# Microcontroller.net
KiCad netlist of a schematic drawn in Altium Designer
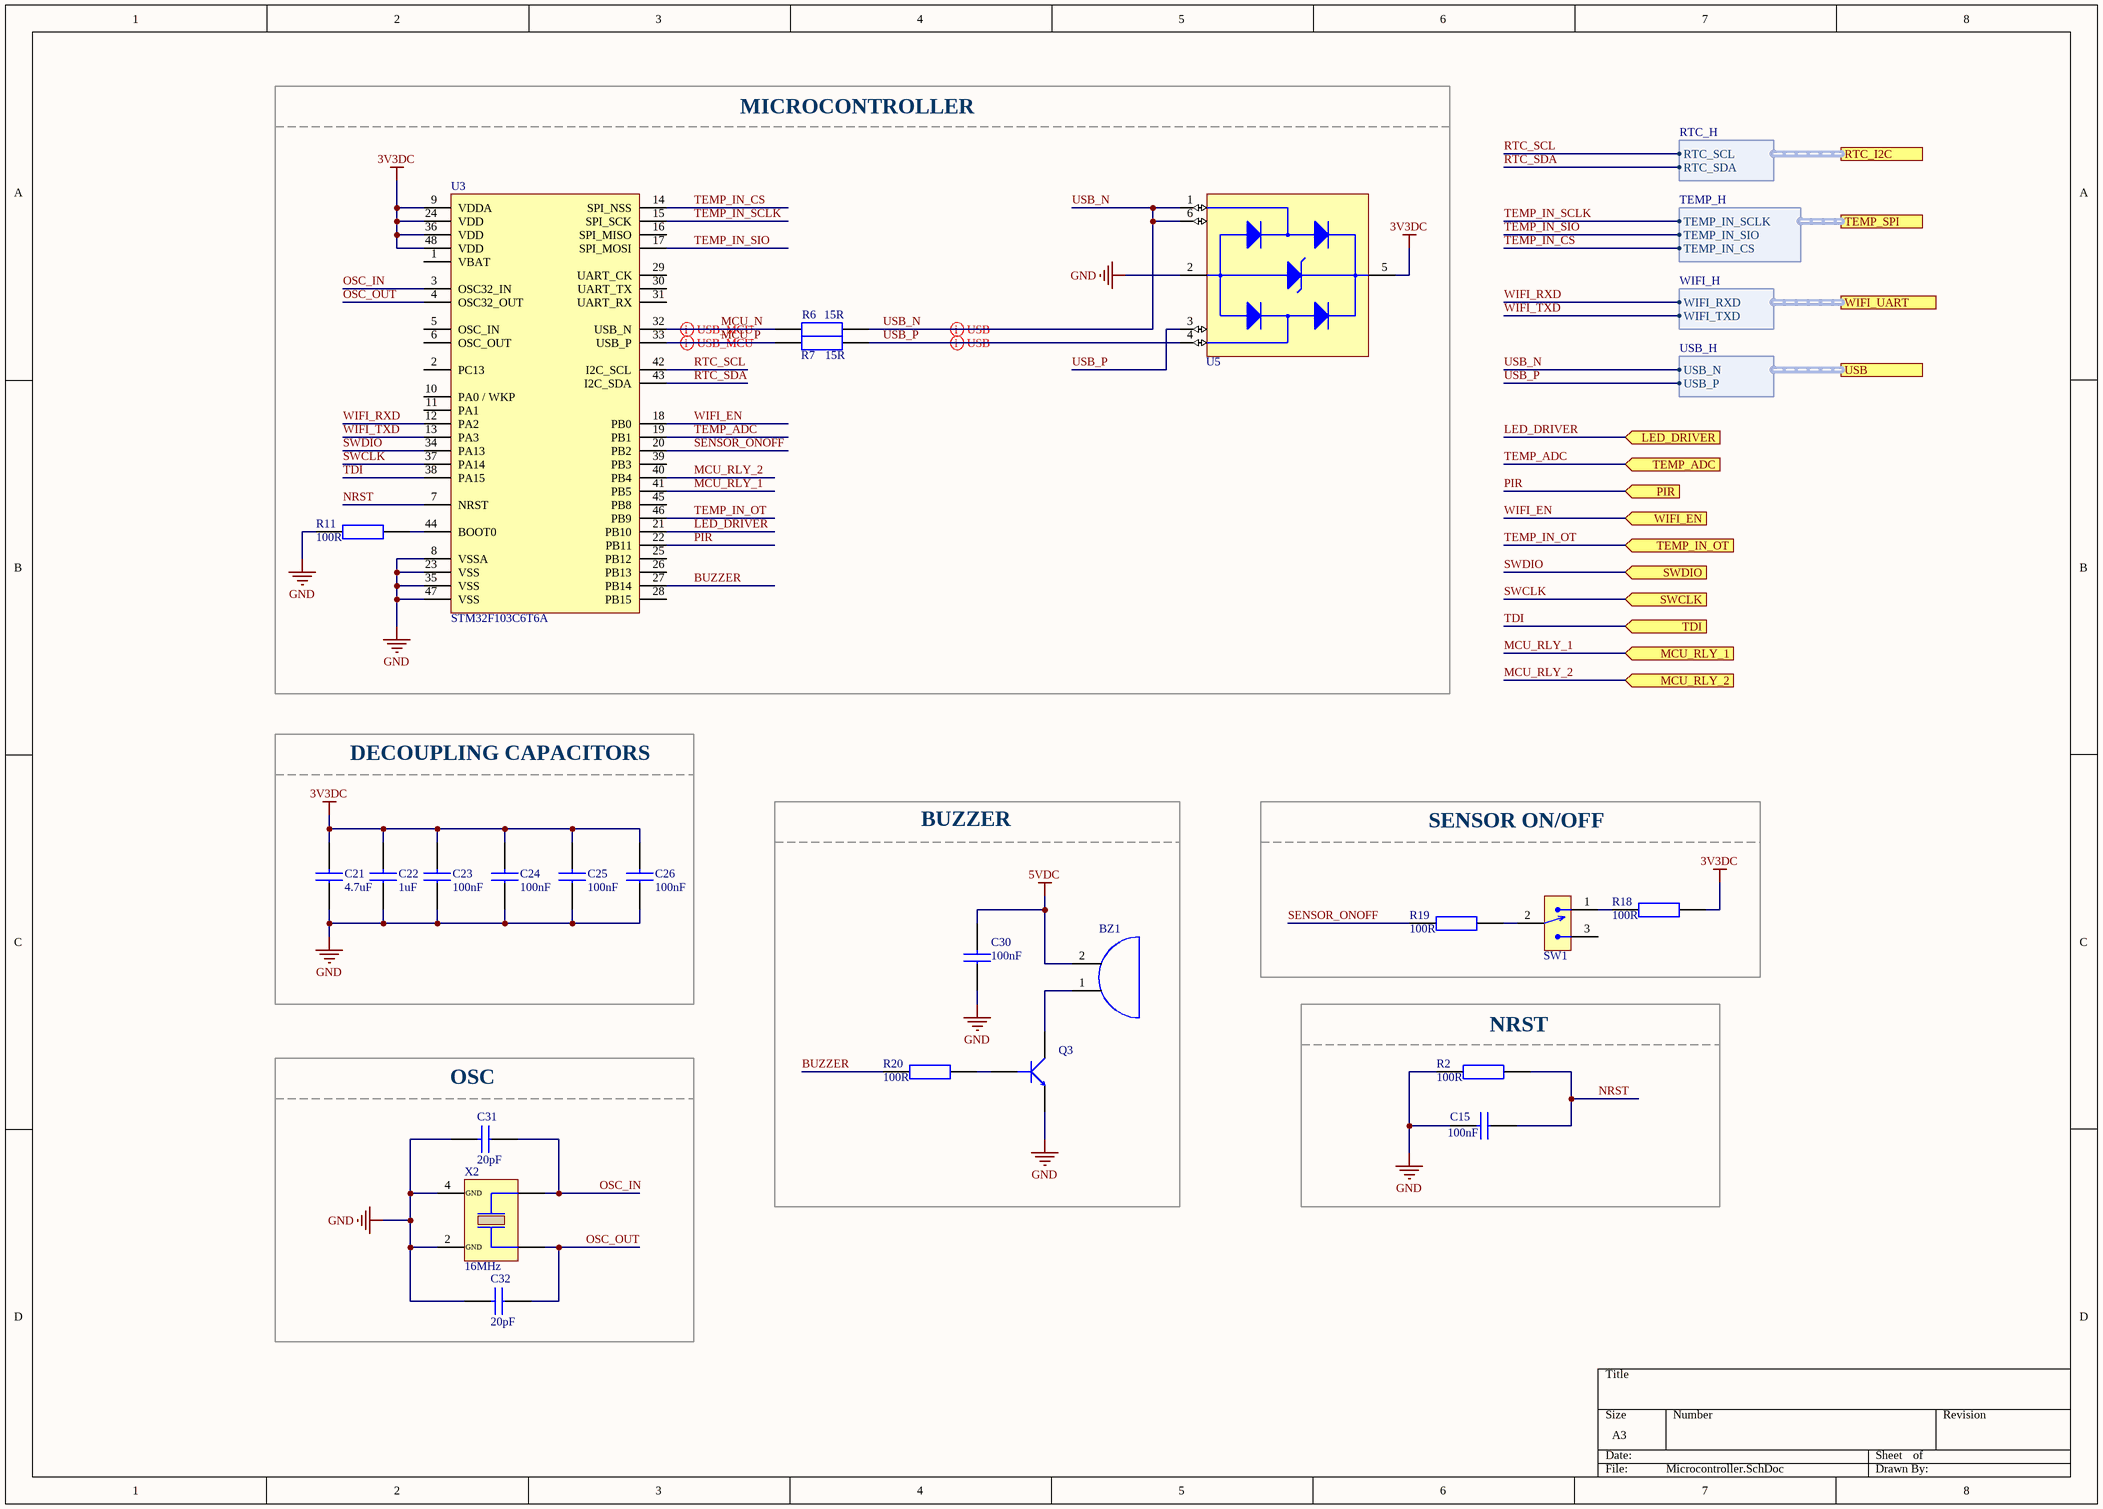
[diagram p0: Microcontroller.SchDoc]

(export (version "E")
  (design (tool "Eeschema 10.0.6"))
  (components
    (comp (ref "BZ1")
      (value "CMI-9605IC-0580T")
      (footprint "CMI-9605IC")
      (description "Buzzers Indicator, Internally Driven Magnetic 5V 30mA 2.7kHz 80dB @ 5V, 10cm Through Hole PC Pins")
      (fields (field (name "MANUFACTURER") "CUI Devices") (field (name "DESIGNED BY") "BERK"))
      (libsource (lib "GuvenlikSistemi_Library") (part "CMI-9605IC-0580T"))
    )
    (comp (ref "C15")
      (value "C0603C104K5RACTU")
      (footprint "CAP_0603")
      (description "CAP CER 100nF %10 0603 SMD")
      (fields
        (field (name "MANUFACTURER") "KEMET")
        (field (name "TOLERANCE") "10%")
        (field (name "CAPACITANCE") "100nF")
        (field (name "DESIGNED BY") "BERK")
      )
      (libsource (lib "GuvenlikSistemi_Library") (part "CAP CER 100nF 0603"))
    )
    (comp (ref "C21")
      (value "CL21A475KAQNNNE")
      (footprint "CAP_0805")
      (description "CAP CER 4.7uF %10 0805")
      (fields
        (field (name "MANUFACTURER") "Samsung")
        (field (name "TOLERANCE") "10%")
        (field (name "CAPACITANCE") "4.7uF")
        (field (name "DESIGNED BY") "BERK")
      )
      (libsource (lib "GuvenlikSistemi_Library") (part "CAP CER 4.7uF 0805"))
    )
    (comp (ref "C22")
      (value "CL21B105KBFNNNE")
      (footprint "CAP_0805")
      (description "CAP CER 1uF %10 0805")
      (fields
        (field (name "MANUFACTURER") "Samsung")
        (field (name "TOLERANCE") "10%")
        (field (name "CAPACITANCE") "1uF")
        (field (name "DESIGNED BY") "BERK")
      )
      (libsource (lib "GuvenlikSistemi_Library") (part "CAP CER 1uF 0805"))
    )
    (comp (ref "C23")
      (value "C0603C104K5RACTU")
      (footprint "CAP_0603")
      (description "CAP CER 100nF %10 0603 SMD")
      (fields
        (field (name "MANUFACTURER") "KEMET")
        (field (name "TOLERANCE") "10%")
        (field (name "CAPACITANCE") "100nF")
        (field (name "DESIGNED BY") "BERK")
      )
      (libsource (lib "GuvenlikSistemi_Library") (part "CAP CER 100nF 0603"))
    )
    (comp (ref "C24")
      (value "C0603C104K5RACTU")
      (footprint "CAP_0603")
      (description "CAP CER 100nF %10 0603 SMD")
      (fields
        (field (name "MANUFACTURER") "KEMET")
        (field (name "TOLERANCE") "10%")
        (field (name "CAPACITANCE") "100nF")
        (field (name "DESIGNED BY") "BERK")
      )
      (libsource (lib "GuvenlikSistemi_Library") (part "CAP CER 100nF 0603"))
    )
    (comp (ref "C25")
      (value "C0603C104K5RACTU")
      (footprint "CAP_0603")
      (description "CAP CER 100nF %10 0603 SMD")
      (fields
        (field (name "MANUFACTURER") "KEMET")
        (field (name "TOLERANCE") "10%")
        (field (name "CAPACITANCE") "100nF")
        (field (name "DESIGNED BY") "BERK")
      )
      (libsource (lib "GuvenlikSistemi_Library") (part "CAP CER 100nF 0603"))
    )
    (comp (ref "C26")
      (value "C0603C104K5RACTU")
      (footprint "CAP_0603")
      (description "CAP CER 100nF %10 0603 SMD")
      (fields
        (field (name "MANUFACTURER") "KEMET")
        (field (name "TOLERANCE") "10%")
        (field (name "CAPACITANCE") "100nF")
        (field (name "DESIGNED BY") "BERK")
      )
      (libsource (lib "GuvenlikSistemi_Library") (part "CAP CER 100nF 0603"))
    )
    (comp (ref "C30")
      (value "CL21B104KBCNNNC")
      (footprint "CAP_0805")
      (description "CAP CER 100nF %10 0805")
      (fields
        (field (name "MANUFACTURER") "Samsung")
        (field (name "TOLERANCE") "10%")
        (field (name "CAPACITANCE") "100nF")
        (field (name "DESIGNED BY") "BERK")
      )
      (libsource (lib "GuvenlikSistemi_Library") (part "CAP CER 100nF 0805"))
    )
    (comp (ref "C31")
      (value "CL10C200JB8NNNC")
      (footprint "CAP_0603")
      (description "CAP CER 20pF %5 0603 SMD")
      (fields
        (field (name "MANUFACTURER") "Samsung")
        (field (name "TOLERANCE") "5%")
        (field (name "CAPACITANCE") "20pF")
        (field (name "DESIGNED BY") "BERK")
      )
      (libsource (lib "GuvenlikSistemi_Library") (part "CAP CER 20pF 0603"))
    )
    (comp (ref "C32")
      (value "CL10C200JB8NNNC")
      (footprint "CAP_0603")
      (description "CAP CER 20pF %5 0603 SMD")
      (fields
        (field (name "MANUFACTURER") "Samsung")
        (field (name "TOLERANCE") "5%")
        (field (name "CAPACITANCE") "20pF")
        (field (name "DESIGNED BY") "BERK")
      )
      (libsource (lib "GuvenlikSistemi_Library") (part "CAP CER 20pF 0603"))
    )
    (comp (ref "Q3")
      (value "MMBT3904-7-F")
      (footprint "SOT-23F")
      (description "Transistor General Purpose BJT NPN 40 Volt 0.2A Automotive 3-Pin SOT-23")
      (fields (field (name "MANUFACTURER") "Diodes Zetex") (field (name "DESIGNED BY") "BERK"))
      (libsource (lib "GuvenlikSistemi_Library") (part "MMBT3904-7-F"))
    )
    (comp (ref "R2")
      (value "RC0603JR-07100RL")
      (footprint "RES_0603")
      (description "RES 100 %5 OHM 0603 SMD")
      (fields
        (field (name "MANUFACTURER") "Yageo")
        (field (name "TOLERANCE") "5%")
        (field (name "RESISTANCE") "100R")
        (field (name "DESIGNED BY") "BERK")
      )
      (libsource (lib "GuvenlikSistemi_Library") (part "RES 100 OHM 0603"))
    )
    (comp (ref "R6")
      (value "RC0603JR-0715RL")
      (footprint "RES_0603")
      (description "RES 15 %5 OHM 0603 SMD")
      (fields
        (field (name "MANUFACTURER") "Yageo")
        (field (name "TOLERANCE") "5%")
        (field (name "RESISTANCE") "15R")
        (field (name "DESIGNED BY") "BERK")
      )
      (libsource (lib "GuvenlikSistemi_Library") (part "RES 15 OHM 0603"))
    )
    (comp (ref "R7")
      (value "RC0603JR-0715RL")
      (footprint "RES_0603")
      (description "RES 15 %5 OHM 0603 SMD")
      (fields
        (field (name "MANUFACTURER") "Yageo")
        (field (name "TOLERANCE") "5%")
        (field (name "RESISTANCE") "15R")
        (field (name "DESIGNED BY") "BERK")
      )
      (libsource (lib "GuvenlikSistemi_Library") (part "RES 15 OHM 0603"))
    )
    (comp (ref "R11")
      (value "RC0603JR-07100RL")
      (footprint "RES_0603")
      (description "RES 100 %5 OHM 0603 SMD")
      (fields
        (field (name "MANUFACTURER") "Yageo")
        (field (name "TOLERANCE") "5%")
        (field (name "RESISTANCE") "100R")
        (field (name "DESIGNED BY") "BERK")
      )
      (libsource (lib "GuvenlikSistemi_Library") (part "RES 100 OHM 0603"))
    )
    (comp (ref "R18")
      (value "RC0603JR-07100RL")
      (footprint "RES_0603")
      (description "RES 100 %5 OHM 0603 SMD")
      (fields
        (field (name "MANUFACTURER") "Yageo")
        (field (name "TOLERANCE") "5%")
        (field (name "RESISTANCE") "100R")
        (field (name "DESIGNED BY") "BERK")
      )
      (libsource (lib "GuvenlikSistemi_Library") (part "RES 100 OHM 0603"))
    )
    (comp (ref "R19")
      (value "RC0603JR-07100RL")
      (footprint "RES_0603")
      (description "RES 100 %5 OHM 0603 SMD")
      (fields
        (field (name "MANUFACTURER") "Yageo")
        (field (name "TOLERANCE") "5%")
        (field (name "RESISTANCE") "100R")
        (field (name "DESIGNED BY") "BERK")
      )
      (libsource (lib "") (part "RES 100 OHM 0603_1"))
    )
    (comp (ref "R20")
      (value "RC0603JR-07100RL")
      (footprint "RES_0603")
      (description "RES 100 %5 OHM 0603 SMD")
      (fields
        (field (name "MANUFACTURER") "Yageo")
        (field (name "TOLERANCE") "5%")
        (field (name "RESISTANCE") "100R")
        (field (name "DESIGNED BY") "BERK")
      )
      (libsource (lib "GuvenlikSistemi_Library") (part "RES 100 OHM 0603"))
    )
    (comp (ref "SW1")
      (value "EG1215AA")
      (footprint "EG1215AA")
      (description "Slide Switch, SPDT, 0.025A, 24V, SMD")
      (fields
        (field (name "MANUFACTURER") "E-Switch")
        (field (name "TOLERANCE") "4.95%")
        (field (name "DESIGNED BY") "BERK")
      )
      (libsource (lib "GuvenlikSistemi_Library") (part "EG1215AA"))
    )
    (comp (ref "U3")
      (value "STM32F103C6T6A")
      (footprint "LQFP-48")
      (description "MCU 32-bit STM32F ARM Cortex M3 RISC 32KB Flash 2.5V/3.3V 48-Pin LQFP Tray")
      (fields (field (name "MANUFACTURER") "STMicroelectronics") (field (name "DESIGNED BY") "BERK"))
      (libsource (lib "GuvenlikSistemi_Library") (part "STM32F103C6T6A"))
    )
    (comp (ref "U5")
      (value "USBLC6-2SC6")
      (footprint "SOT23-6L")
      (description "TVS DIODE 5.25V 17V SOT23-6")
      (fields (field (name "MANUFACTURER") "STMicroelectronics") (field (name "DESIGNED BY") "BERK"))
      (libsource (lib "GuvenlikSistemi_Library") (part "USB PROTECTION"))
    )
    (comp (ref "X2")
      (value "ECS-160-20-30B-TR")
      (footprint "ECS")
      (description "CRYSTAL 16.0000MHZ 20PF SMD")
      (fields
        (field (name "MANUFACTURER") "ECS International")
        (field (name "TOLERANCE") "50ppm")
        (field (name "FREQUENCY") "16MHz")
        (field (name "DESIGNED BY") "BERK")
      )
      (libsource (lib "GuvenlikSistemi_Library") (part "CRYSTAL 16MHz"))
    )
  )
  (nets
    (net (code "5") (name "/BUZZER") (class "Default")
      (node (ref "R20") (pin "1") (pinfunction "1_1") (pintype "passive"))
      (node (ref "U3") (pin "27") (pinfunction "PB14_27") (pintype "passive"))
    )
    (net (code "6") (name "/LED_DRIVER") (class "Default")
      (node (ref "U3") (pin "21") (pinfunction "PB10_21") (pintype "passive"))
    )
    (net (code "7") (name "/MCU_N") (class "Default")
      (node (ref "R6") (pin "1") (pinfunction "1_1") (pintype "passive"))
      (node (ref "U3") (pin "32") (pinfunction "USB_N_32") (pintype "passive"))
    )
    (net (code "8") (name "/MCU_P") (class "Default")
      (node (ref "R7") (pin "1") (pinfunction "1_1") (pintype "passive"))
      (node (ref "U3") (pin "33") (pinfunction "USB_P_33") (pintype "passive"))
    )
    (net (code "9") (name "/MCU_RLY_1") (class "Default")
      (node (ref "U3") (pin "41") (pinfunction "PB5_41") (pintype "passive"))
    )
    (net (code "10") (name "/MCU_RLY_2") (class "Default")
      (node (ref "U3") (pin "40") (pinfunction "PB4_40") (pintype "passive"))
    )
    (net (code "11") (name "/NRST") (class "Default")
      (node (ref "C15") (pin "1") (pinfunction "1_1") (pintype "passive"))
      (node (ref "R2") (pin "2") (pinfunction "2_2") (pintype "passive"))
      (node (ref "U3") (pin "7") (pinfunction "NRST_7") (pintype "passive"))
    )
    (net (code "12") (name "/OSC_IN") (class "Default")
      (node (ref "C31") (pin "1") (pinfunction "1_1") (pintype "passive"))
      (node (ref "U3") (pin "3") (pinfunction "OSC32_IN_3") (pintype "passive"))
      (node (ref "X2") (pin "3") (pinfunction "3_3") (pintype "passive"))
    )
    (net (code "13") (name "/OSC_OUT") (class "Default")
      (node (ref "C32") (pin "1") (pinfunction "1_1") (pintype "passive"))
      (node (ref "U3") (pin "4") (pinfunction "OSC32_OUT_4") (pintype "passive"))
      (node (ref "X2") (pin "1") (pinfunction "1_1") (pintype "passive"))
    )
    (net (code "14") (name "/PIR") (class "Default")
      (node (ref "U3") (pin "22") (pinfunction "PB11_22") (pintype "passive"))
    )
    (net (code "15") (name "/RTC_SCL") (class "Default")
      (node (ref "U3") (pin "42") (pinfunction "I2C_SCL_42") (pintype "passive"))
    )
    (net (code "16") (name "/RTC_SDA") (class "Default")
      (node (ref "U3") (pin "43") (pinfunction "I2C_SDA_43") (pintype "passive"))
    )
    (net (code "17") (name "/SENSOR_ONOFF") (class "Default")
      (node (ref "R19") (pin "2") (pinfunction "2_2") (pintype "passive"))
      (node (ref "U3") (pin "20") (pinfunction "PB2_20") (pintype "passive"))
    )
    (net (code "18") (name "/SWCLK") (class "Default")
      (node (ref "U3") (pin "37") (pinfunction "PA14_37") (pintype "passive"))
    )
    (net (code "19") (name "/SWDIO") (class "Default")
      (node (ref "U3") (pin "34") (pinfunction "PA13_34") (pintype "passive"))
    )
    (net (code "20") (name "/TDI") (class "Default")
      (node (ref "U3") (pin "38") (pinfunction "PA15_38") (pintype "passive"))
    )
    (net (code "21") (name "/TEMP_ADC") (class "Default")
      (node (ref "U3") (pin "19") (pinfunction "PB1_19") (pintype "passive"))
    )
    (net (code "22") (name "/TEMP_IN_CS") (class "Default")
      (node (ref "U3") (pin "14") (pinfunction "SPI_NSS_14") (pintype "passive"))
    )
    (net (code "23") (name "/TEMP_IN_OT") (class "Default")
      (node (ref "U3") (pin "46") (pinfunction "PB9_46") (pintype "passive"))
    )
    (net (code "24") (name "/TEMP_IN_SCLK") (class "Default")
      (node (ref "U3") (pin "15") (pinfunction "SPI_SCK_15") (pintype "passive"))
    )
    (net (code "25") (name "/TEMP_IN_SIO") (class "Default")
      (node (ref "U3") (pin "17") (pinfunction "SPI_MOSI_17") (pintype "passive"))
    )
    (net (code "26") (name "/USB_N") (class "Default")
      (node (ref "R6") (pin "2") (pinfunction "2_2") (pintype "passive"))
      (node (ref "U5") (pin "1") (pinfunction "I/O1_1") (pintype "bidirectional"))
      (node (ref "U5") (pin "6") (pinfunction "I/O1_6") (pintype "bidirectional"))
    )
    (net (code "27") (name "/USB_P") (class "Default")
      (node (ref "R7") (pin "2") (pinfunction "2_2") (pintype "passive"))
      (node (ref "U5") (pin "3") (pinfunction "I/O2_3") (pintype "bidirectional"))
      (node (ref "U5") (pin "4") (pinfunction "I/O2_4") (pintype "bidirectional"))
    )
    (net (code "28") (name "/WIFI_EN") (class "Default")
      (node (ref "U3") (pin "18") (pinfunction "PB0_18") (pintype "passive"))
    )
    (net (code "29") (name "/WIFI_RXD") (class "Default")
      (node (ref "U3") (pin "12") (pinfunction "PA2_12") (pintype "passive"))
    )
    (net (code "30") (name "/WIFI_TXD") (class "Default")
      (node (ref "U3") (pin "13") (pinfunction "PA3_13") (pintype "passive"))
    )
    (net (code "35") (name "3V3DC") (class "Default")
      (node (ref "C21") (pin "2") (pinfunction "2_2") (pintype "passive"))
      (node (ref "C22") (pin "2") (pinfunction "2_2") (pintype "passive"))
      (node (ref "C23") (pin "2") (pinfunction "2_2") (pintype "passive"))
      (node (ref "C24") (pin "2") (pinfunction "2_2") (pintype "passive"))
      (node (ref "C25") (pin "2") (pinfunction "2_2") (pintype "passive"))
      (node (ref "C26") (pin "2") (pinfunction "2_2") (pintype "passive"))
      (node (ref "R18") (pin "2") (pinfunction "2_2") (pintype "passive"))
      (node (ref "U3") (pin "24") (pinfunction "VDD_24") (pintype "passive"))
      (node (ref "U3") (pin "36") (pinfunction "VDD_36") (pintype "passive"))
      (node (ref "U3") (pin "48") (pinfunction "VDD_48") (pintype "passive"))
      (node (ref "U3") (pin "9") (pinfunction "VDDA_9") (pintype "passive"))
      (node (ref "U5") (pin "5") (pinfunction "VBUS_5") (pintype "power_in"))
    )
    (net (code "36") (name "5VDC") (class "Default")
      (node (ref "BZ1") (pin "2") (pinfunction "2_2") (pintype "passive"))
      (node (ref "C30") (pin "2") (pinfunction "2_2") (pintype "passive"))
    )
    (net (code "37") (name "GND") (class "Default")
      (node (ref "C15") (pin "2") (pinfunction "2_2") (pintype "passive"))
      (node (ref "C21") (pin "1") (pinfunction "1_1") (pintype "passive"))
      (node (ref "C22") (pin "1") (pinfunction "1_1") (pintype "passive"))
      (node (ref "C23") (pin "1") (pinfunction "1_1") (pintype "passive"))
      (node (ref "C24") (pin "1") (pinfunction "1_1") (pintype "passive"))
      (node (ref "C25") (pin "1") (pinfunction "1_1") (pintype "passive"))
      (node (ref "C26") (pin "1") (pinfunction "1_1") (pintype "passive"))
      (node (ref "C30") (pin "1") (pinfunction "1_1") (pintype "passive"))
      (node (ref "C31") (pin "2") (pinfunction "2_2") (pintype "passive"))
      (node (ref "C32") (pin "2") (pinfunction "2_2") (pintype "passive"))
      (node (ref "Q3") (pin "2") (pinfunction "E_2") (pintype "power_in"))
      (node (ref "R11") (pin "1") (pinfunction "1_1") (pintype "passive"))
      (node (ref "R2") (pin "1") (pinfunction "1_1") (pintype "passive"))
      (node (ref "U3") (pin "23") (pinfunction "VSS_23") (pintype "passive"))
      (node (ref "U3") (pin "35") (pinfunction "VSS_35") (pintype "passive"))
      (node (ref "U3") (pin "47") (pinfunction "VSS_47") (pintype "passive"))
      (node (ref "U3") (pin "8") (pinfunction "VSSA_8") (pintype "passive"))
      (node (ref "U5") (pin "2") (pinfunction "GND_2") (pintype "power_in"))
      (node (ref "X2") (pin "2") (pinfunction "GND_2") (pintype "passive"))
      (node (ref "X2") (pin "4") (pinfunction "GND_4") (pintype "passive"))
    )
    (net (code "38") (name "Net-(Q3-B)") (class "Default")
      (node (ref "Q3") (pin "1") (pinfunction "B_1") (pintype "power_in"))
      (node (ref "R20") (pin "2") (pinfunction "2_2") (pintype "passive"))
    )
    (net (code "39") (name "Net-(Q3-C)") (class "Default")
      (node (ref "BZ1") (pin "1") (pinfunction "1_1") (pintype "passive"))
      (node (ref "Q3") (pin "3") (pinfunction "C_3") (pintype "power_in"))
    )
    (net (code "40") (name "Net-(R18-Pad1)") (class "Default")
      (node (ref "R18") (pin "1") (pinfunction "1_1") (pintype "passive"))
      (node (ref "SW1") (pin "1") (pinfunction "1_1") (pintype "passive"))
    )
    (net (code "41") (name "Net-(R19-Pad1)") (class "Default")
      (node (ref "R19") (pin "1") (pinfunction "1_1") (pintype "passive"))
      (node (ref "SW1") (pin "2") (pinfunction "2_2") (pintype "passive"))
    )
    (net (code "42") (name "Net-(U3-BOOT0)") (class "Default")
      (node (ref "R11") (pin "2") (pinfunction "2_2") (pintype "passive"))
      (node (ref "U3") (pin "44") (pinfunction "BOOT0_44") (pintype "passive"))
    )
    (net (code "43") (name "unconnected-(SW1-Pad3)") (class "Default")
      (node (ref "SW1") (pin "3") (pinfunction "3_3") (pintype "passive"))
    )
    (net (code "44") (name "unconnected-(U3-OSC_IN-Pad5)") (class "Default")
      (node (ref "U3") (pin "5") (pinfunction "OSC_IN_5") (pintype "passive"))
    )
    (net (code "45") (name "unconnected-(U3-OSC_OUT-Pad6)") (class "Default")
      (node (ref "U3") (pin "6") (pinfunction "OSC_OUT_6") (pintype "passive"))
    )
    (net (code "46") (name "unconnected-(U3-PA0_{slash}_WKP-Pad10)") (class "Default")
      (node (ref "U3") (pin "10") (pinfunction "PA0_/_WKP_10") (pintype "passive"))
    )
    (net (code "47") (name "unconnected-(U3-PA1-Pad11)") (class "Default")
      (node (ref "U3") (pin "11") (pinfunction "PA1_11") (pintype "passive"))
    )
    (net (code "48") (name "unconnected-(U3-PB3-Pad39)") (class "Default")
      (node (ref "U3") (pin "39") (pinfunction "PB3_39") (pintype "passive"))
    )
    (net (code "49") (name "unconnected-(U3-PB8-Pad45)") (class "Default")
      (node (ref "U3") (pin "45") (pinfunction "PB8_45") (pintype "passive"))
    )
    (net (code "50") (name "unconnected-(U3-PB12-Pad25)") (class "Default")
      (node (ref "U3") (pin "25") (pinfunction "PB12_25") (pintype "passive"))
    )
    (net (code "51") (name "unconnected-(U3-PB13-Pad26)") (class "Default")
      (node (ref "U3") (pin "26") (pinfunction "PB13_26") (pintype "passive"))
    )
    (net (code "52") (name "unconnected-(U3-PB15-Pad28)") (class "Default")
      (node (ref "U3") (pin "28") (pinfunction "PB15_28") (pintype "passive"))
    )
    (net (code "53") (name "unconnected-(U3-PC13-Pad2)") (class "Default")
      (node (ref "U3") (pin "2") (pinfunction "PC13_2") (pintype "passive"))
    )
    (net (code "54") (name "unconnected-(U3-SPI_MISO-Pad16)") (class "Default")
      (node (ref "U3") (pin "16") (pinfunction "SPI_MISO_16") (pintype "passive"))
    )
    (net (code "55") (name "unconnected-(U3-UART_CK-Pad29)") (class "Default")
      (node (ref "U3") (pin "29") (pinfunction "UART_CK_29") (pintype "passive"))
    )
    (net (code "56") (name "unconnected-(U3-UART_RX-Pad31)") (class "Default")
      (node (ref "U3") (pin "31") (pinfunction "UART_RX_31") (pintype "passive"))
    )
    (net (code "57") (name "unconnected-(U3-UART_TX-Pad30)") (class "Default")
      (node (ref "U3") (pin "30") (pinfunction "UART_TX_30") (pintype "passive"))
    )
    (net (code "58") (name "unconnected-(U3-VBAT-Pad1)") (class "Default")
      (node (ref "U3") (pin "1") (pinfunction "VBAT_1") (pintype "passive"))
    )
  )
)
